# iridia-tam-right-board.net
KiCad netlist of a schematic drawn in EAGLE
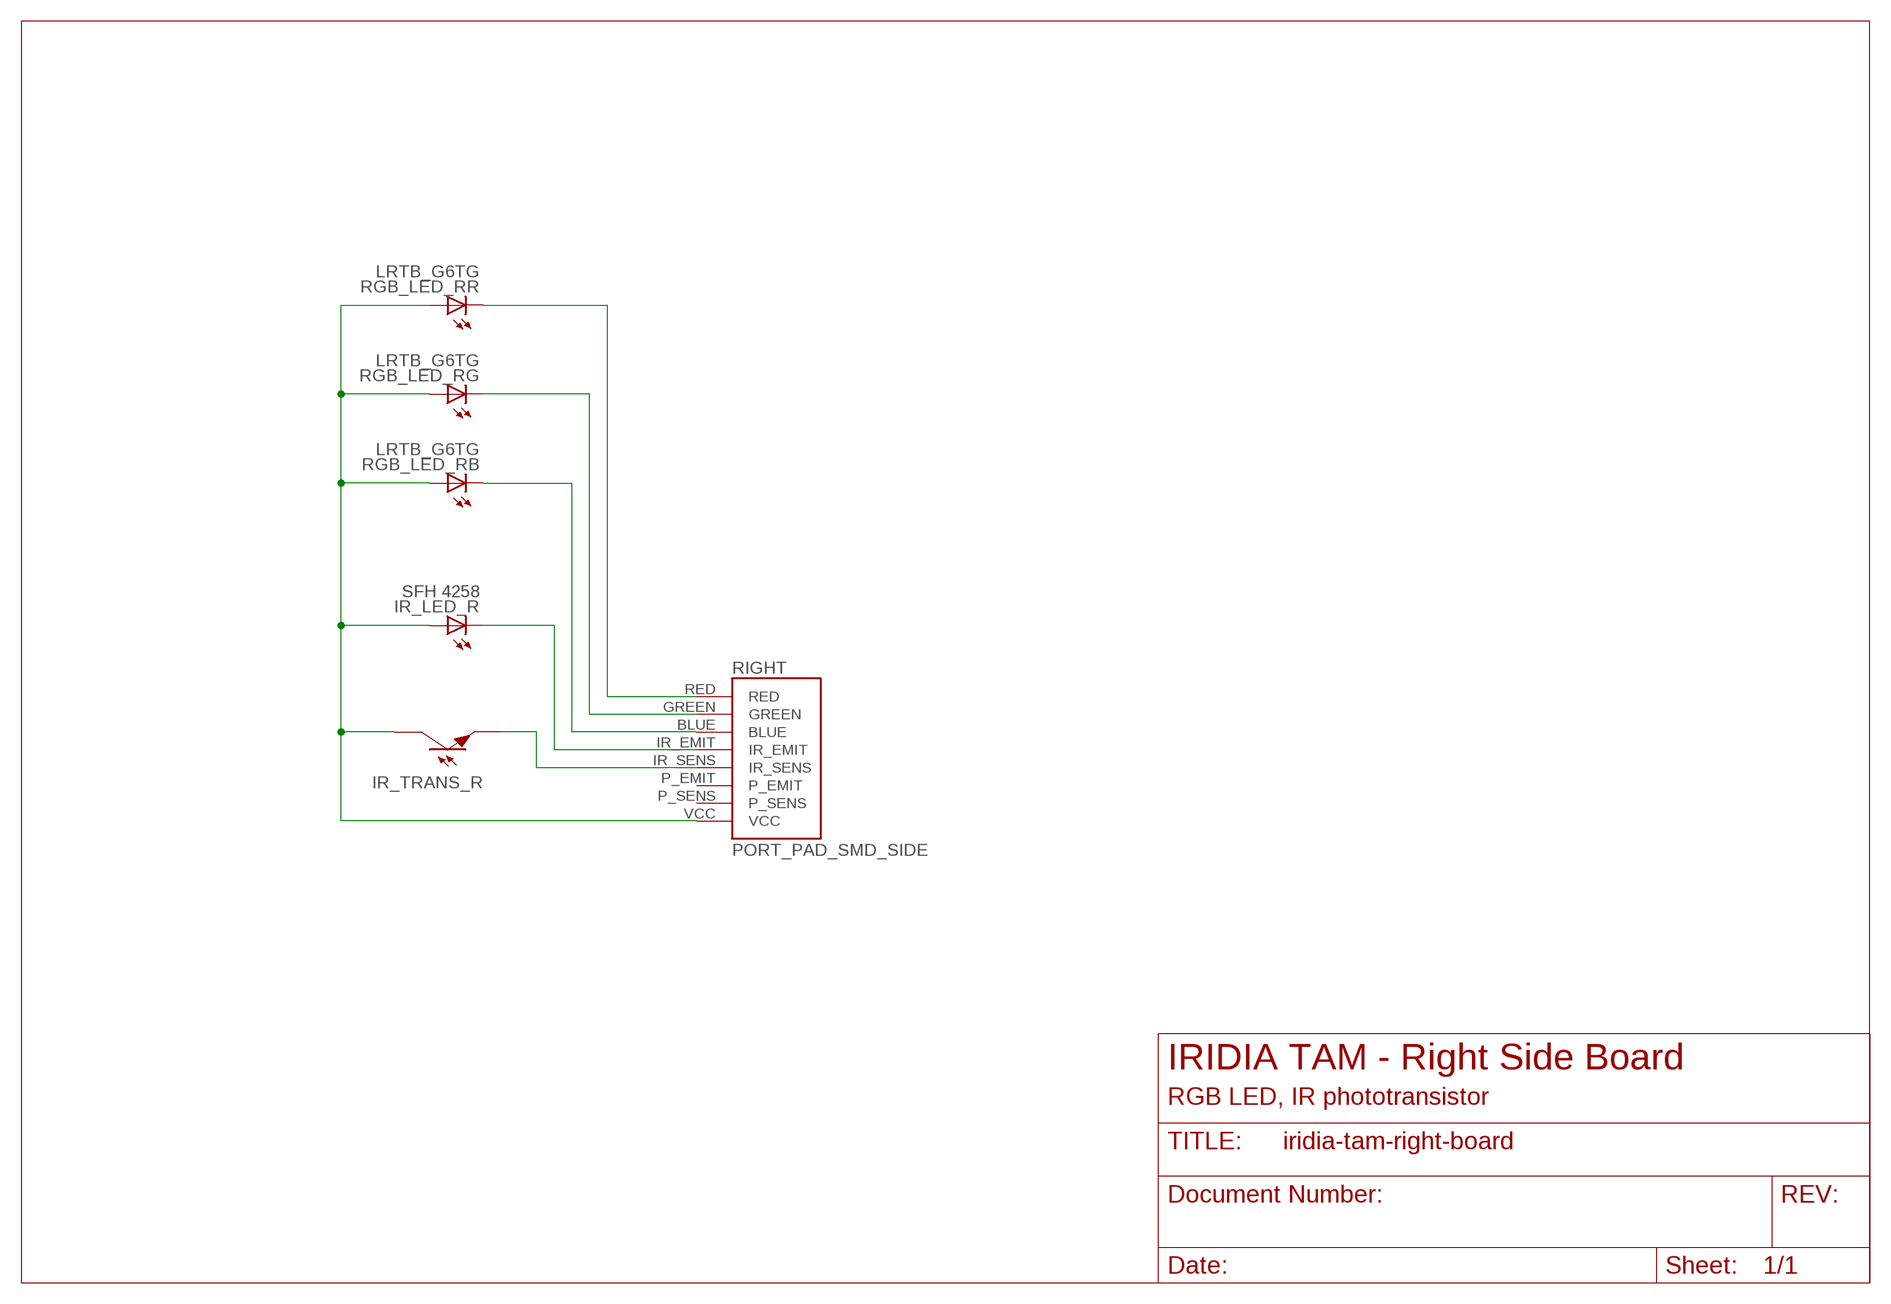
[diagram p0: schematic, sheet 1]

(export (version "E")
  (design (tool "Eeschema 10.0.6"))
  (components
    (comp (ref "IR_LED_R")
      (value "SFH 4258")
      (footprint "eagle-import:P-LCC-4-1C-3A")
      (libsource (lib "eagle-import") (part "LEDP-LCC-4"))
    )
    (comp (ref "IR_TRANS_R")
      (value "SFH 320 FA")
      (footprint "eagle-import:P-LCC-2-TRANS")
      (libsource (lib "eagle-import") (part "IR_TRANSP-LCC-2"))
    )
    (comp (ref "RGB_LED_R")
      (value "LRTB_G6TG")
      (footprint "eagle-import:P-LCC-6_TOPLED")
      (libsource (lib "eagle-import") (part "MULTILED_LRTB_G6TG"))
    )
    (comp (ref "RIGHT")
      (value "PORT_PAD_SMD_SIDE")
      (footprint "eagle-import:PORT_PAD_SMD_SIDE")
      (libsource (lib "eagle-import") (part "PORT_PAD_SMD_SIDE"))
    )
  )
  (nets
    (net (code "1") (name "Net-(IR_LED_R-C)") (class "Default")
      (node (ref "IR_LED_R") (pin "C@1") (pinfunction "C_C@1") (pintype "passive"))
      (node (ref "RIGHT") (pin "IR_EMIT") (pinfunction "IR_EMIT_IR_EMIT") (pintype "bidirectional"))
    )
    (net (code "2") (name "Net-(IR_TRANS_R-PadE)") (class "Default")
      (node (ref "IR_TRANS_R") (pin "E") (pinfunction "E_E") (pintype "passive"))
      (node (ref "RIGHT") (pin "IR_SENS") (pinfunction "IR_SENS_IR_SENS") (pintype "bidirectional"))
    )
    (net (code "3") (name "Net-(RGB_LED_RA-A)") (class "Default")
      (node (ref "IR_LED_R") (pin "A@2") (pinfunction "A_A@2") (pintype "passive"))
      (node (ref "IR_LED_R") (pin "A@3") (pinfunction "A_A@3") (pintype "passive"))
      (node (ref "IR_LED_R") (pin "A@4") (pinfunction "A_A@4") (pintype "passive"))
      (node (ref "IR_TRANS_R") (pin "COL") (pinfunction "COL_COL") (pintype "passive"))
      (node (ref "RGB_LED_R") (pin "A1") (pinfunction "A_A1") (pintype "passive"))
      (node (ref "RGB_LED_R") (pin "A2") (pinfunction "A_A2") (pintype "passive"))
      (node (ref "RGB_LED_R") (pin "A3") (pinfunction "A_A3") (pintype "passive"))
      (node (ref "RIGHT") (pin "VCC") (pinfunction "VCC_VCC") (pintype "bidirectional"))
    )
    (net (code "4") (name "Net-(RGB_LED_RA-C)") (class "Default")
      (node (ref "RGB_LED_R") (pin "C3") (pinfunction "C_C3") (pintype "passive"))
      (node (ref "RIGHT") (pin "BLUE") (pinfunction "BLUE_BLUE") (pintype "bidirectional"))
    )
    (net (code "5") (name "Net-(RGB_LED_RB-C)") (class "Default")
      (node (ref "RGB_LED_R") (pin "C2") (pinfunction "C_C2") (pintype "passive"))
      (node (ref "RIGHT") (pin "GREEN") (pinfunction "GREEN_GREEN") (pintype "bidirectional"))
    )
    (net (code "6") (name "Net-(RGB_LED_RC-C)") (class "Default")
      (node (ref "RGB_LED_R") (pin "C1") (pinfunction "C_C1") (pintype "passive"))
      (node (ref "RIGHT") (pin "RED") (pinfunction "RED_RED") (pintype "bidirectional"))
    )
    (net (code "7") (name "unconnected-(RIGHT-PadP_EMIT)") (class "Default")
      (node (ref "RIGHT") (pin "P_EMIT") (pinfunction "P_EMIT_P_EMIT") (pintype "bidirectional"))
    )
    (net (code "8") (name "unconnected-(RIGHT-PadP_SENS)") (class "Default")
      (node (ref "RIGHT") (pin "P_SENS") (pinfunction "P_SENS_P_SENS") (pintype "bidirectional"))
    )
  )
)
